# Wisp_v04.net
KiCad netlist of a schematic drawn in EAGLE
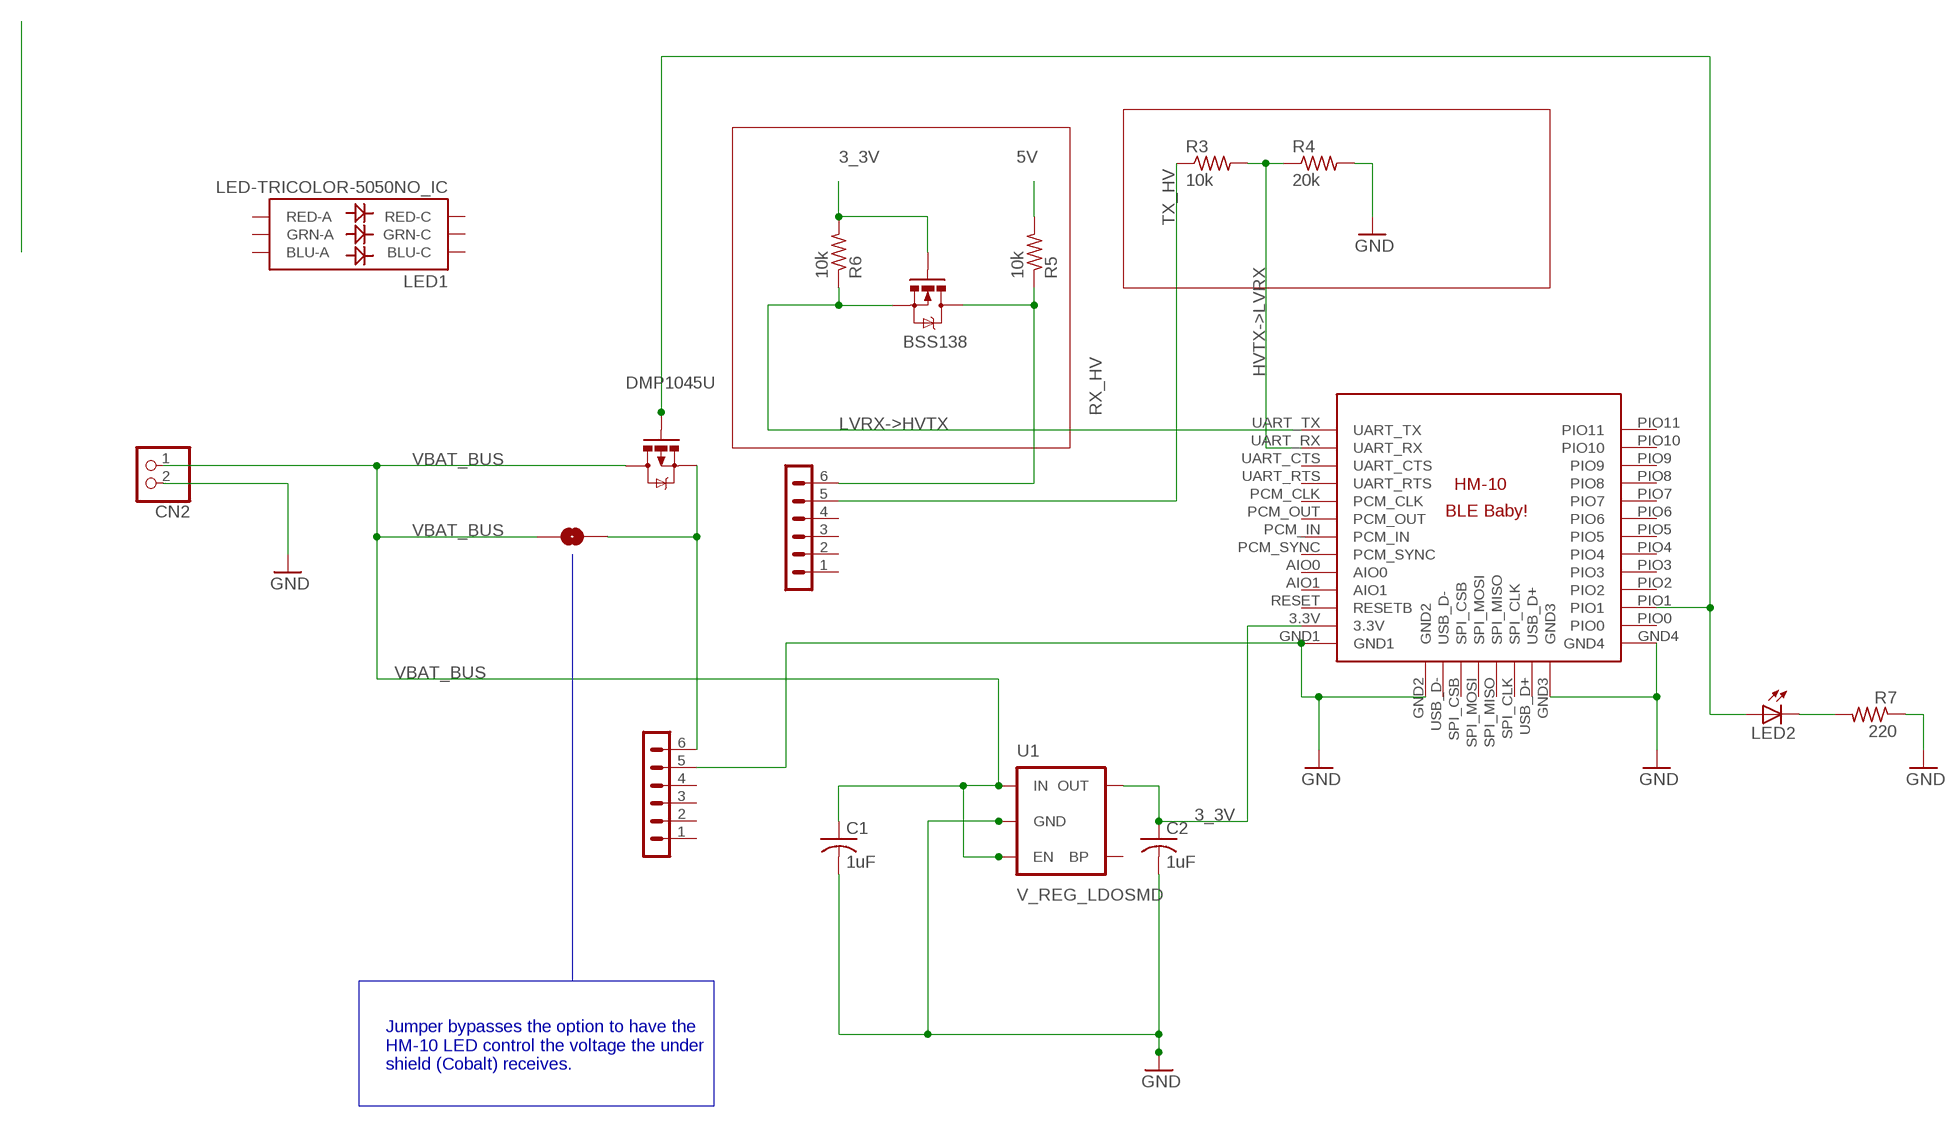
[diagram p0: schematic, sheet 1]

(export (version "E")
  (design (tool "Eeschema 10.0.6"))
  (components
    (comp (ref "BSS138")
      (value "MOSFET-NCHANNELSMD")
      (footprint "eagle-import:SOT23-3")
      (libsource (lib "eagle-import") (part "MOSFET-NCHANNELSMD"))
    )
    (comp (ref "C1")
      (value "1uF")
      (footprint "eagle-import:C0805K")
      (libsource (lib "eagle-import") (part "C-USC0805K"))
    )
    (comp (ref "C2")
      (value "1uF")
      (footprint "eagle-import:C0805K")
      (libsource (lib "eagle-import") (part "C-USC0805K"))
    )
    (comp (ref "CN2")
      (value "JST_2PIN-THM")
      (footprint "eagle-import:JST-PH-2-THM")
      (libsource (lib "eagle-import") (part "JST_2PIN-THM"))
    )
    (comp (ref "DMP1045U")
      (value "MOSFET-PCHANNELSMD")
      (footprint "eagle-import:SOT23-3")
      (libsource (lib "eagle-import") (part "MOSFET-PCHANNELSMD"))
    )
    (comp (ref "LED1")
      (value "LED-TRICOLOR-5050NO_IC")
      (footprint "eagle-import:LED-TRICOLOR-5050")
      (libsource (lib "eagle-import") (part "LED-TRICOLOR-5050NO_IC"))
    )
    (comp (ref "LED2")
      (value "LED0603")
      (footprint "eagle-import:LED-0603")
      (libsource (lib "eagle-import") (part "LED0603"))
    )
    (comp (ref "R3")
      (value "10k")
      (footprint "eagle-import:R0402")
      (libsource (lib "eagle-import") (part "R-US_R0402"))
    )
    (comp (ref "R4")
      (value "20k")
      (footprint "eagle-import:R0402")
      (libsource (lib "eagle-import") (part "R-US_R0402"))
    )
    (comp (ref "R5")
      (value "10k")
      (footprint "eagle-import:R0402")
      (libsource (lib "eagle-import") (part "R-US_R0402"))
    )
    (comp (ref "R6")
      (value "10k")
      (footprint "eagle-import:R0402")
      (libsource (lib "eagle-import") (part "R-US_R0402"))
    )
    (comp (ref "R7")
      (value "220")
      (footprint "eagle-import:R0402")
      (libsource (lib "eagle-import") (part "R-US_R0402"))
    )
    (comp (ref "SJ2")
      (value "SOLDERJUMPERNO")
      (footprint "eagle-import:SJ_2S-NO")
      (libsource (lib "eagle-import") (part "SOLDERJUMPERNO"))
    )
    (comp (ref "U$1")
      (value "BLE-HM-10")
      (footprint "eagle-import:BLE-HM-10")
      (libsource (lib "eagle-import") (part "BLE-HM-10"))
    )
    (comp (ref "U$4")
      (value "1X6_SHORT_ROUND")
      (footprint "eagle-import:1X6_SHORT_ROUND")
      (libsource (lib "eagle-import") (part "1X6_SHORT_ROUND"))
    )
    (comp (ref "U$5")
      (value "1X6_SHORT_ROUND")
      (footprint "eagle-import:1X6_SHORT_ROUND")
      (libsource (lib "eagle-import") (part "1X6_SHORT_ROUND"))
    )
    (comp (ref "U1")
      (value "V_REG_LDOSMD")
      (footprint "eagle-import:SOT23-5")
      (libsource (lib "eagle-import") (part "V_REG_LDOSMD"))
    )
  )
  (nets
    (net (code "1") (name "/3_3V") (class "Default")
      (node (ref "BSS138") (pin "1") (pinfunction "G_1") (pintype "passive"))
      (node (ref "C2") (pin "1") (pinfunction "1_1") (pintype "passive"))
      (node (ref "R6") (pin "2") (pinfunction "2_2") (pintype "passive"))
      (node (ref "U$1") (pin "3.3V") (pinfunction "3.3V_3.3V") (pintype "bidirectional"))
      (node (ref "U1") (pin "5") (pinfunction "OUT_5") (pintype "passive"))
    )
    (net (code "2") (name "/5V") (class "Default")
      (node (ref "R5") (pin "2") (pinfunction "2_2") (pintype "passive"))
    )
    (net (code "3") (name "/HVTX->LVRX") (class "Default")
      (node (ref "R3") (pin "2") (pinfunction "2_2") (pintype "passive"))
      (node (ref "R4") (pin "1") (pinfunction "1_1") (pintype "passive"))
      (node (ref "U$1") (pin "UART_RX") (pinfunction "UART_RX_UART_RX") (pintype "bidirectional"))
    )
    (net (code "4") (name "/LVRX->HVTX") (class "Default")
      (node (ref "BSS138") (pin "2") (pinfunction "S_2") (pintype "passive"))
      (node (ref "R6") (pin "1") (pinfunction "1_1") (pintype "passive"))
      (node (ref "U$1") (pin "UART_TX") (pinfunction "UART_TX_UART_TX") (pintype "bidirectional"))
    )
    (net (code "5") (name "/RX_HV") (class "Default")
      (node (ref "BSS138") (pin "3") (pinfunction "D_3") (pintype "passive"))
      (node (ref "R5") (pin "1") (pinfunction "1_1") (pintype "passive"))
      (node (ref "U$4") (pin "6") (pinfunction "6_6") (pintype "passive"))
    )
    (net (code "6") (name "/TX_HV") (class "Default")
      (node (ref "R3") (pin "1") (pinfunction "1_1") (pintype "passive"))
      (node (ref "U$4") (pin "5") (pinfunction "5_5") (pintype "passive"))
    )
    (net (code "7") (name "/VBAT_BUS") (class "Default")
      (node (ref "C1") (pin "1") (pinfunction "1_1") (pintype "passive"))
      (node (ref "CN2") (pin "1") (pinfunction "2_1") (pintype "passive"))
      (node (ref "DMP1045U") (pin "3") (pinfunction "D_3") (pintype "passive"))
      (node (ref "SJ2") (pin "2") (pinfunction "2_2") (pintype "passive"))
      (node (ref "U1") (pin "1") (pinfunction "IN_1") (pintype "input"))
      (node (ref "U1") (pin "3") (pinfunction "EN_3") (pintype "input"))
    )
    (net (code "8") (name "GND") (class "Default")
      (node (ref "C1") (pin "2") (pinfunction "2_2") (pintype "passive"))
      (node (ref "C2") (pin "2") (pinfunction "2_2") (pintype "passive"))
      (node (ref "CN2") (pin "2") (pinfunction "1_2") (pintype "passive"))
      (node (ref "R4") (pin "2") (pinfunction "2_2") (pintype "passive"))
      (node (ref "R7") (pin "1") (pinfunction "1_1") (pintype "passive"))
      (node (ref "U$1") (pin "GND1") (pinfunction "GND1_GND1") (pintype "bidirectional"))
      (node (ref "U$1") (pin "GND2") (pinfunction "GND2_GND2") (pintype "bidirectional"))
      (node (ref "U$1") (pin "GND3") (pinfunction "GND3_GND3") (pintype "bidirectional"))
      (node (ref "U$1") (pin "GND4") (pinfunction "GND4_GND4") (pintype "bidirectional"))
      (node (ref "U$5") (pin "5") (pinfunction "5_5") (pintype "passive"))
      (node (ref "U1") (pin "2") (pinfunction "GND_2") (pintype "input"))
    )
    (net (code "9") (name "Net-(DMP1045U-G)") (class "Default")
      (node (ref "DMP1045U") (pin "1") (pinfunction "G_1") (pintype "passive"))
      (node (ref "LED2") (pin "A") (pinfunction "A_A") (pintype "passive"))
      (node (ref "U$1") (pin "PIO1") (pinfunction "PIO1_PIO1") (pintype "bidirectional"))
    )
    (net (code "10") (name "Net-(DMP1045U-S)") (class "Default")
      (node (ref "DMP1045U") (pin "2") (pinfunction "S_2") (pintype "passive"))
      (node (ref "SJ2") (pin "1") (pinfunction "1_1") (pintype "passive"))
      (node (ref "U$5") (pin "6") (pinfunction "6_6") (pintype "passive"))
    )
    (net (code "11") (name "Net-(LED2-PadC)") (class "Default")
      (node (ref "LED2") (pin "C") (pinfunction "C_C") (pintype "passive"))
      (node (ref "R7") (pin "2") (pinfunction "2_2") (pintype "passive"))
    )
    (net (code "12") (name "unconnected-(LED1-BLU-A-Pad3)") (class "Default")
      (node (ref "LED1") (pin "3") (pinfunction "BLU-A_3") (pintype "bidirectional"))
    )
    (net (code "13") (name "unconnected-(LED1-BLU-C-Pad4)") (class "Default")
      (node (ref "LED1") (pin "4") (pinfunction "BLU-C_4") (pintype "bidirectional"))
    )
    (net (code "14") (name "unconnected-(LED1-GRN-A-Pad1)") (class "Default")
      (node (ref "LED1") (pin "1") (pinfunction "GRN-A_1") (pintype "bidirectional"))
    )
    (net (code "15") (name "unconnected-(LED1-GRN-C-Pad6)") (class "Default")
      (node (ref "LED1") (pin "6") (pinfunction "GRN-C_6") (pintype "bidirectional"))
    )
    (net (code "16") (name "unconnected-(LED1-RED-A-Pad2)") (class "Default")
      (node (ref "LED1") (pin "2") (pinfunction "RED-A_2") (pintype "bidirectional"))
    )
    (net (code "17") (name "unconnected-(LED1-RED-C-Pad5)") (class "Default")
      (node (ref "LED1") (pin "5") (pinfunction "RED-C_5") (pintype "bidirectional"))
    )
    (net (code "18") (name "unconnected-(U$1-PadAIO0)") (class "Default")
      (node (ref "U$1") (pin "AIO0") (pinfunction "AIO0_AIO0") (pintype "bidirectional"))
    )
    (net (code "19") (name "unconnected-(U$1-PadAIO1)") (class "Default")
      (node (ref "U$1") (pin "AIO1") (pinfunction "AIO1_AIO1") (pintype "bidirectional"))
    )
    (net (code "20") (name "unconnected-(U$1-PadPCM_CLK)") (class "Default")
      (node (ref "U$1") (pin "PCM_CLK") (pinfunction "PCM_CLK_PCM_CLK") (pintype "bidirectional"))
    )
    (net (code "21") (name "unconnected-(U$1-PadPCM_IN)") (class "Default")
      (node (ref "U$1") (pin "PCM_IN") (pinfunction "PCM_IN_PCM_IN") (pintype "bidirectional"))
    )
    (net (code "22") (name "unconnected-(U$1-PadPCM_OUT)") (class "Default")
      (node (ref "U$1") (pin "PCM_OUT") (pinfunction "PCM_OUT_PCM_OUT") (pintype "bidirectional"))
    )
    (net (code "23") (name "unconnected-(U$1-PadPCM_SYNC)") (class "Default")
      (node (ref "U$1") (pin "PCM_SYNC") (pinfunction "PCM_SYNC_PCM_SYNC") (pintype "bidirectional"))
    )
    (net (code "24") (name "unconnected-(U$1-PadPIO0)") (class "Default")
      (node (ref "U$1") (pin "PIO0") (pinfunction "PIO0_PIO0") (pintype "bidirectional"))
    )
    (net (code "25") (name "unconnected-(U$1-PadPIO2)") (class "Default")
      (node (ref "U$1") (pin "PIO2") (pinfunction "PIO2_PIO2") (pintype "bidirectional"))
    )
    (net (code "26") (name "unconnected-(U$1-PadPIO3)") (class "Default")
      (node (ref "U$1") (pin "PIO3") (pinfunction "PIO3_PIO3") (pintype "bidirectional"))
    )
    (net (code "27") (name "unconnected-(U$1-PadPIO4)") (class "Default")
      (node (ref "U$1") (pin "PIO4") (pinfunction "PIO4_PIO4") (pintype "bidirectional"))
    )
    (net (code "28") (name "unconnected-(U$1-PadPIO5)") (class "Default")
      (node (ref "U$1") (pin "PIO5") (pinfunction "PIO5_PIO5") (pintype "bidirectional"))
    )
    (net (code "29") (name "unconnected-(U$1-PadPIO6)") (class "Default")
      (node (ref "U$1") (pin "PIO6") (pinfunction "PIO6_PIO6") (pintype "bidirectional"))
    )
    (net (code "30") (name "unconnected-(U$1-PadPIO7)") (class "Default")
      (node (ref "U$1") (pin "PIO7") (pinfunction "PIO7_PIO7") (pintype "bidirectional"))
    )
    (net (code "31") (name "unconnected-(U$1-PadPIO8)") (class "Default")
      (node (ref "U$1") (pin "PIO8") (pinfunction "PIO8_PIO8") (pintype "bidirectional"))
    )
    (net (code "32") (name "unconnected-(U$1-PadPIO9)") (class "Default")
      (node (ref "U$1") (pin "PIO9") (pinfunction "PIO9_PIO9") (pintype "bidirectional"))
    )
    (net (code "33") (name "unconnected-(U$1-PadPIO10)") (class "Default")
      (node (ref "U$1") (pin "PIO10") (pinfunction "PIO10_PIO10") (pintype "bidirectional"))
    )
    (net (code "34") (name "unconnected-(U$1-PadPIO11)") (class "Default")
      (node (ref "U$1") (pin "PIO11") (pinfunction "PIO11_PIO11") (pintype "bidirectional"))
    )
    (net (code "35") (name "unconnected-(U$1-PadSPI_CLK)") (class "Default")
      (node (ref "U$1") (pin "SPI_CLK") (pinfunction "SPI_CLK_SPI_CLK") (pintype "bidirectional"))
    )
    (net (code "36") (name "unconnected-(U$1-PadSPI_CSB)") (class "Default")
      (node (ref "U$1") (pin "SPI_CSB") (pinfunction "SPI_CSB_SPI_CSB") (pintype "bidirectional"))
    )
    (net (code "37") (name "unconnected-(U$1-PadSPI_MISO)") (class "Default")
      (node (ref "U$1") (pin "SPI_MISO") (pinfunction "SPI_MISO_SPI_MISO") (pintype "bidirectional"))
    )
    (net (code "38") (name "unconnected-(U$1-PadSPI_MOSI)") (class "Default")
      (node (ref "U$1") (pin "SPI_MOSI") (pinfunction "SPI_MOSI_SPI_MOSI") (pintype "bidirectional"))
    )
    (net (code "39") (name "unconnected-(U$1-PadUART_CTS)") (class "Default")
      (node (ref "U$1") (pin "UART_CTS") (pinfunction "UART_CTS_UART_CTS") (pintype "bidirectional"))
    )
    (net (code "40") (name "unconnected-(U$1-PadUART_RTS)") (class "Default")
      (node (ref "U$1") (pin "UART_RTS") (pinfunction "UART_RTS_UART_RTS") (pintype "bidirectional"))
    )
    (net (code "41") (name "unconnected-(U$1-PadUSB_D+)") (class "Default")
      (node (ref "U$1") (pin "USB_D+") (pinfunction "USB_D+_USB_D+") (pintype "bidirectional"))
    )
    (net (code "42") (name "unconnected-(U$1-PadUSB_D-)") (class "Default")
      (node (ref "U$1") (pin "USB_D-") (pinfunction "USB_D-_USB_D-") (pintype "bidirectional"))
    )
    (net (code "43") (name "unconnected-(U$1-RESETB-PadRESET)") (class "Default")
      (node (ref "U$1") (pin "RESET") (pinfunction "RESETB_RESET") (pintype "bidirectional"))
    )
    (net (code "44") (name "unconnected-(U$4-Pad1)") (class "Default")
      (node (ref "U$4") (pin "1") (pinfunction "1_1") (pintype "passive"))
    )
    (net (code "45") (name "unconnected-(U$4-Pad2)") (class "Default")
      (node (ref "U$4") (pin "2") (pinfunction "2_2") (pintype "passive"))
    )
    (net (code "46") (name "unconnected-(U$4-Pad3)") (class "Default")
      (node (ref "U$4") (pin "3") (pinfunction "3_3") (pintype "passive"))
    )
    (net (code "47") (name "unconnected-(U$4-Pad4)") (class "Default")
      (node (ref "U$4") (pin "4") (pinfunction "4_4") (pintype "passive"))
    )
    (net (code "48") (name "unconnected-(U$5-Pad1)") (class "Default")
      (node (ref "U$5") (pin "1") (pinfunction "1_1") (pintype "passive"))
    )
    (net (code "49") (name "unconnected-(U$5-Pad2)") (class "Default")
      (node (ref "U$5") (pin "2") (pinfunction "2_2") (pintype "passive"))
    )
    (net (code "50") (name "unconnected-(U$5-Pad3)") (class "Default")
      (node (ref "U$5") (pin "3") (pinfunction "3_3") (pintype "passive"))
    )
    (net (code "51") (name "unconnected-(U$5-Pad4)") (class "Default")
      (node (ref "U$5") (pin "4") (pinfunction "4_4") (pintype "passive"))
    )
    (net (code "52") (name "unconnected-(U1-BP-Pad4)") (class "Default")
      (node (ref "U1") (pin "4") (pinfunction "BP_4") (pintype "input"))
    )
  )
)
